# drv8825.net
KiCad netlist of a schematic drawn in EAGLE
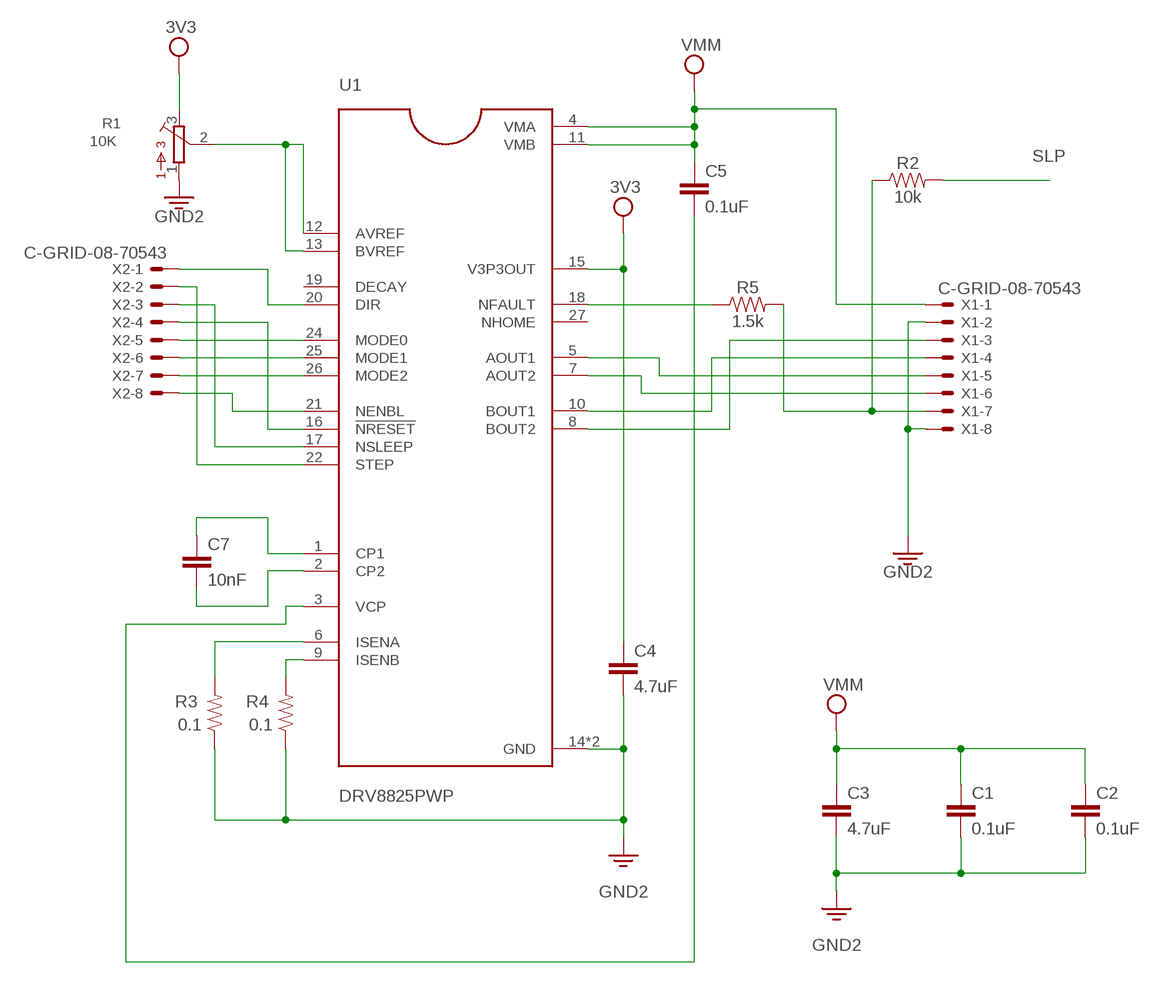
[diagram p0: schematic, sheet 1]

(export (version "E")
  (design (tool "Eeschema 10.0.6"))
  (components
    (comp (ref "C1")
      (value "0.1uF")
      (footprint "eagle-import:0402")
      (libsource (lib "eagle-import") (part "0.1UF-0402-16V-10%"))
    )
    (comp (ref "C2")
      (value "0.1uF")
      (footprint "eagle-import:0402")
      (libsource (lib "eagle-import") (part "0.1UF-0402-16V-10%"))
    )
    (comp (ref "C3")
      (value "4.7uF")
      (footprint "eagle-import:0603")
      (libsource (lib "eagle-import") (part "4.7UF0603"))
    )
    (comp (ref "C4")
      (value "4.7uF")
      (footprint "eagle-import:0603")
      (libsource (lib "eagle-import") (part "4.7UF0603"))
    )
    (comp (ref "C5")
      (value "0.1uF")
      (footprint "eagle-import:0402")
      (libsource (lib "eagle-import") (part "0.1UF-0402-16V-10%"))
    )
    (comp (ref "C7")
      (value "10nF")
      (footprint "eagle-import:0603")
      (libsource (lib "eagle-import") (part "10NF-0603-50V-10%"))
    )
    (comp (ref "R1")
      (value "10K")
      (footprint "eagle-import:3362R")
      (libsource (lib "eagle-import") (part "3362R"))
    )
    (comp (ref "R2")
      (value "10k")
      (footprint "eagle-import:0603")
      (libsource (lib "eagle-import") (part "10KOHM-0603-1/10W-1%"))
    )
    (comp (ref "R3")
      (value "0.1")
      (footprint "eagle-import:1210")
      (libsource (lib "eagle-import") (part "0.1OHM-1210-1/2W-1%"))
    )
    (comp (ref "R4")
      (value "0.1")
      (footprint "eagle-import:1210")
      (libsource (lib "eagle-import") (part "0.1OHM-1210-1/2W-1%"))
    )
    (comp (ref "R5")
      (value "1.5k")
      (footprint "eagle-import:0603")
      (libsource (lib "eagle-import") (part "1.5KOHM-0603-1/10W-1%"))
    )
    (comp (ref "U1")
      (value "DRV8825PWP")
      (footprint "eagle-import:SOP65P640X120-28N")
      (fields (field (name "DIGI-KEY_PART_NUMBER") "296-28915-5-ND") (field (name "MF") "Texas Instruments"))
      (libsource (lib "eagle-import") (part "DRV8825PWP"))
    )
    (comp (ref "X1")
      (value "C-GRID-08-70543")
      (footprint "eagle-import:70543-08")
      (fields (field (name "MF") "MOLEX"))
      (libsource (lib "eagle-import") (part "C-GRID-08-70543"))
    )
    (comp (ref "X2")
      (value "C-GRID-08-70543")
      (footprint "eagle-import:70543-08")
      (fields (field (name "MF") "MOLEX"))
      (libsource (lib "eagle-import") (part "C-GRID-08-70543"))
    )
  )
  (nets
    (net (code "1") (name "/SLP") (class "Default")
      (node (ref "R2") (pin "2") (pinfunction "2_2") (pintype "passive"))
    )
    (net (code "2") (name "3V3") (class "Default")
      (node (ref "C1") (pin "1") (pinfunction "1_1") (pintype "passive"))
      (node (ref "C2") (pin "1") (pinfunction "1_1") (pintype "passive"))
      (node (ref "C3") (pin "1") (pinfunction "1_1") (pintype "passive"))
      (node (ref "C4") (pin "1") (pinfunction "1_1") (pintype "passive"))
      (node (ref "C5") (pin "1") (pinfunction "1_1") (pintype "passive"))
      (node (ref "R1") (pin "3") (pinfunction "3_3") (pintype "passive"))
      (node (ref "U1") (pin "11") (pinfunction "VMB_11") (pintype "power_in"))
      (node (ref "U1") (pin "15") (pinfunction "V3P3OUT_15") (pintype "output"))
      (node (ref "U1") (pin "4") (pinfunction "VMA_4") (pintype "power_in"))
      (node (ref "X1") (pin "1") (pinfunction "S_1") (pintype "passive"))
    )
    (net (code "3") (name "GND2") (class "Default")
      (node (ref "C1") (pin "2") (pinfunction "2_2") (pintype "passive"))
      (node (ref "C2") (pin "2") (pinfunction "2_2") (pintype "passive"))
      (node (ref "C3") (pin "2") (pinfunction "2_2") (pintype "passive"))
      (node (ref "C4") (pin "2") (pinfunction "2_2") (pintype "passive"))
      (node (ref "R1") (pin "1") (pinfunction "1_1") (pintype "passive"))
      (node (ref "R3") (pin "1") (pinfunction "1_1") (pintype "passive"))
      (node (ref "R4") (pin "1") (pinfunction "1_1") (pintype "passive"))
      (node (ref "U1") (pin "14") (pinfunction "GND_14") (pintype "passive"))
      (node (ref "U1") (pin "28") (pinfunction "GND_28") (pintype "passive"))
      (node (ref "X1") (pin "2") (pinfunction "S_2") (pintype "passive"))
      (node (ref "X1") (pin "8") (pinfunction "S_8") (pintype "passive"))
    )
    (net (code "4") (name "Net-(U1-AOUT1)") (class "Default")
      (node (ref "U1") (pin "5") (pinfunction "AOUT1_5") (pintype "output"))
      (node (ref "X1") (pin "5") (pinfunction "S_5") (pintype "passive"))
    )
    (net (code "5") (name "Net-(U1-AOUT2)") (class "Default")
      (node (ref "U1") (pin "7") (pinfunction "AOUT2_7") (pintype "output"))
      (node (ref "X1") (pin "6") (pinfunction "S_6") (pintype "passive"))
    )
    (net (code "6") (name "Net-(U1-AVREF)") (class "Default")
      (node (ref "R1") (pin "2") (pinfunction "2_2") (pintype "passive"))
      (node (ref "U1") (pin "12") (pinfunction "AVREF_12") (pintype "input"))
      (node (ref "U1") (pin "13") (pinfunction "BVREF_13") (pintype "input"))
    )
    (net (code "7") (name "Net-(U1-BOUT1)") (class "Default")
      (node (ref "U1") (pin "10") (pinfunction "BOUT1_10") (pintype "output"))
      (node (ref "X1") (pin "4") (pinfunction "S_4") (pintype "passive"))
    )
    (net (code "8") (name "Net-(U1-BOUT2)") (class "Default")
      (node (ref "U1") (pin "8") (pinfunction "BOUT2_8") (pintype "output"))
      (node (ref "X1") (pin "3") (pinfunction "S_3") (pintype "passive"))
    )
    (net (code "9") (name "Net-(U1-CP1)") (class "Default")
      (node (ref "C7") (pin "1") (pinfunction "1_1") (pintype "passive"))
      (node (ref "U1") (pin "1") (pinfunction "CP1_1") (pintype "bidirectional"))
    )
    (net (code "10") (name "Net-(U1-CP2)") (class "Default")
      (node (ref "C7") (pin "2") (pinfunction "2_2") (pintype "passive"))
      (node (ref "U1") (pin "2") (pinfunction "CP2_2") (pintype "bidirectional"))
    )
    (net (code "11") (name "Net-(U1-DIR)") (class "Default")
      (node (ref "U1") (pin "20") (pinfunction "DIR_20") (pintype "input"))
      (node (ref "X2") (pin "1") (pinfunction "S_1") (pintype "passive"))
    )
    (net (code "12") (name "Net-(U1-ISENA)") (class "Default")
      (node (ref "R3") (pin "2") (pinfunction "2_2") (pintype "passive"))
      (node (ref "U1") (pin "6") (pinfunction "ISENA_6") (pintype "bidirectional"))
    )
    (net (code "13") (name "Net-(U1-ISENB)") (class "Default")
      (node (ref "R4") (pin "2") (pinfunction "2_2") (pintype "passive"))
      (node (ref "U1") (pin "9") (pinfunction "ISENB_9") (pintype "bidirectional"))
    )
    (net (code "14") (name "Net-(U1-MODE0)") (class "Default")
      (node (ref "U1") (pin "24") (pinfunction "MODE0_24") (pintype "input"))
      (node (ref "X2") (pin "5") (pinfunction "S_5") (pintype "passive"))
    )
    (net (code "15") (name "Net-(U1-MODE1)") (class "Default")
      (node (ref "U1") (pin "25") (pinfunction "MODE1_25") (pintype "input"))
      (node (ref "X2") (pin "6") (pinfunction "S_6") (pintype "passive"))
    )
    (net (code "16") (name "Net-(U1-MODE2)") (class "Default")
      (node (ref "U1") (pin "26") (pinfunction "MODE2_26") (pintype "input"))
      (node (ref "X2") (pin "7") (pinfunction "S_7") (pintype "passive"))
    )
    (net (code "17") (name "Net-(U1-NENBL)") (class "Default")
      (node (ref "U1") (pin "21") (pinfunction "NENBL_21") (pintype "input"))
      (node (ref "X2") (pin "8") (pinfunction "S_8") (pintype "passive"))
    )
    (net (code "18") (name "Net-(U1-NFAULT)") (class "Default")
      (node (ref "R5") (pin "1") (pinfunction "1_1") (pintype "passive"))
      (node (ref "U1") (pin "18") (pinfunction "NFAULT_18") (pintype "output"))
    )
    (net (code "19") (name "Net-(U1-NSLEEP)") (class "Default")
      (node (ref "U1") (pin "17") (pinfunction "NSLEEP_17") (pintype "input"))
      (node (ref "X2") (pin "3") (pinfunction "S_3") (pintype "passive"))
    )
    (net (code "20") (name "Net-(U1-STEP)") (class "Default")
      (node (ref "U1") (pin "22") (pinfunction "STEP_22") (pintype "input"))
      (node (ref "X2") (pin "2") (pinfunction "S_2") (pintype "passive"))
    )
    (net (code "21") (name "Net-(U1-VCP)") (class "Default")
      (node (ref "C5") (pin "2") (pinfunction "2_2") (pintype "passive"))
      (node (ref "U1") (pin "3") (pinfunction "VCP_3") (pintype "bidirectional"))
    )
    (net (code "22") (name "Net-(U1-~{NRESET})") (class "Default")
      (node (ref "U1") (pin "16") (pinfunction "~{NRESET}_16") (pintype "input"))
      (node (ref "X2") (pin "4") (pinfunction "S_4") (pintype "passive"))
    )
    (net (code "23") (name "Net-(X1G-S)") (class "Default")
      (node (ref "R2") (pin "1") (pinfunction "1_1") (pintype "passive"))
      (node (ref "R5") (pin "2") (pinfunction "2_2") (pintype "passive"))
      (node (ref "X1") (pin "7") (pinfunction "S_7") (pintype "passive"))
    )
    (net (code "24") (name "unconnected-(U1-DECAY-Pad19)") (class "Default")
      (node (ref "U1") (pin "19") (pinfunction "DECAY_19") (pintype "input"))
    )
    (net (code "25") (name "unconnected-(U1-NHOME-Pad27)") (class "Default")
      (node (ref "U1") (pin "27") (pinfunction "NHOME_27") (pintype "output"))
    )
  )
)
